# lvc-strobe-generator.net
KiCad netlist of a schematic drawn in EAGLE
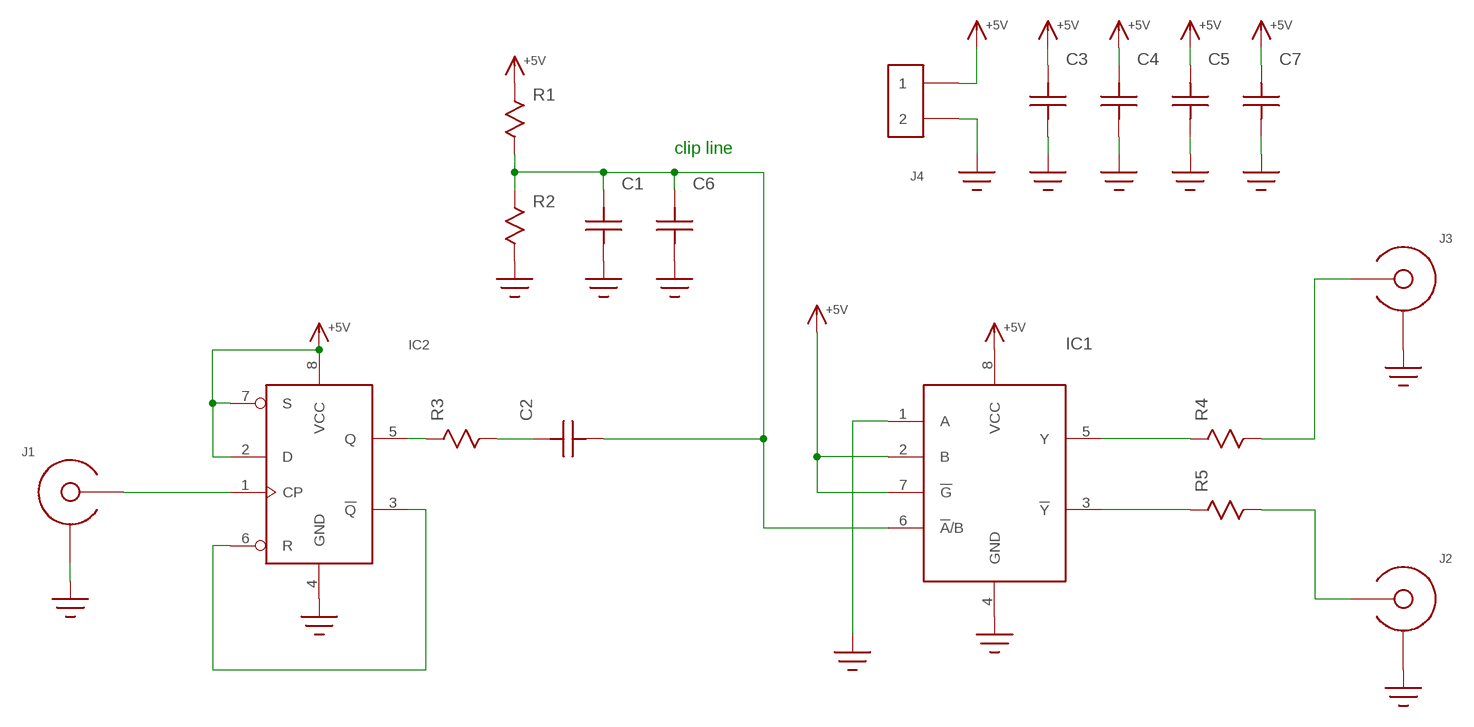
[diagram p0: schematic, sheet 1]

(export (version "E")
  (design (tool "Eeschema 10.0.6"))
  (components
    (comp (ref "C1") (value "C") (footprint "eagle-import:C0402") (libsource (lib "eagle-import") (part "C")))
    (comp (ref "C2") (value "C") (footprint "eagle-import:C0402") (libsource (lib "eagle-import") (part "C")))
    (comp (ref "C3")
      (value "C1206")
      (footprint "eagle-import:1206")
      (libsource (lib "eagle-import") (part "C1206"))
    )
    (comp (ref "C4")
      (value "C0603")
      (footprint "eagle-import:C0603")
      (libsource (lib "eagle-import") (part "C0603"))
    )
    (comp (ref "C5")
      (value "C0603")
      (footprint "eagle-import:C0603")
      (libsource (lib "eagle-import") (part "C0603"))
    )
    (comp (ref "C6") (value "C") (footprint "eagle-import:C0402") (libsource (lib "eagle-import") (part "C")))
    (comp (ref "C7")
      (value "C0603")
      (footprint "eagle-import:C0603")
      (libsource (lib "eagle-import") (part "C0603"))
    )
    (comp (ref "IC1")
      (value "74LVC2G157")
      (footprint "eagle-import:SSOP8")
      (libsource (lib "eagle-import") (part "74LVC2G157"))
    )
    (comp (ref "IC2")
      (value "74LVC2G74")
      (footprint "eagle-import:SSOP8")
      (libsource (lib "eagle-import") (part "74LVC2G74"))
    )
    (comp (ref "J1")
      (value "SMA-EDGE-LAUNCH4L-4020-TAPER-FIXED")
      (footprint "eagle-import:SMA_EDGE_LAUNCH_4L_4020_TAPER_FIXED")
      (libsource (lib "eagle-import") (part "SMA-EDGE-LAUNCH4L-4020-TAPER-FIXED"))
    )
    (comp (ref "J2")
      (value "SMA-EDGE-LAUNCH4L-4020-TAPER-FIXED")
      (footprint "eagle-import:SMA_EDGE_LAUNCH_4L_4020_TAPER_FIXED")
      (libsource (lib "eagle-import") (part "SMA-EDGE-LAUNCH4L-4020-TAPER-FIXED"))
    )
    (comp (ref "J3")
      (value "SMA-EDGE-LAUNCH4L-4020-TAPER-FIXED")
      (footprint "eagle-import:SMA_EDGE_LAUNCH_4L_4020_TAPER_FIXED")
      (libsource (lib "eagle-import") (part "SMA-EDGE-LAUNCH4L-4020-TAPER-FIXED"))
    )
    (comp (ref "J4")
      (value "HEADER_2PIN")
      (footprint "eagle-import:HEADER_2PIN")
      (libsource (lib "eagle-import") (part "HEADER_2PIN"))
    )
    (comp (ref "R1")
      (value "R0603")
      (footprint "eagle-import:R0603")
      (libsource (lib "eagle-import") (part "R0603"))
    )
    (comp (ref "R2")
      (value "R0603")
      (footprint "eagle-import:R0603")
      (libsource (lib "eagle-import") (part "R0603"))
    )
    (comp (ref "R3")
      (value "R0402")
      (footprint "eagle-import:0402")
      (libsource (lib "eagle-import") (part "R0402"))
    )
    (comp (ref "R4")
      (value "R0603")
      (footprint "eagle-import:R0603")
      (libsource (lib "eagle-import") (part "R0603"))
    )
    (comp (ref "R5")
      (value "R0603")
      (footprint "eagle-import:R0603")
      (libsource (lib "eagle-import") (part "R0603"))
    )
  )
  (nets
    (net (code "1") (name "+5V") (class "Default")
      (node (ref "C3") (pin "P$2") (pinfunction "P$2_P$2") (pintype "bidirectional"))
      (node (ref "C4") (pin "P$2") (pinfunction "P$2_P$2") (pintype "bidirectional"))
      (node (ref "C5") (pin "P$2") (pinfunction "P$2_P$2") (pintype "bidirectional"))
      (node (ref "C7") (pin "P$2") (pinfunction "P$2_P$2") (pintype "bidirectional"))
      (node (ref "IC1") (pin "2") (pinfunction "B_2") (pintype "bidirectional"))
      (node (ref "IC1") (pin "7") (pinfunction "~{G}_7") (pintype "bidirectional"))
      (node (ref "IC1") (pin "8") (pinfunction "VCC_8") (pintype "bidirectional"))
      (node (ref "IC2") (pin "2") (pinfunction "D_2") (pintype "bidirectional"))
      (node (ref "IC2") (pin "7") (pinfunction "S_7") (pintype "bidirectional"))
      (node (ref "IC2") (pin "8") (pinfunction "VCC_8") (pintype "bidirectional"))
      (node (ref "J4") (pin "1") (pinfunction "1_1") (pintype "bidirectional"))
      (node (ref "R1") (pin "P$1") (pinfunction "P$3_P$1") (pintype "bidirectional"))
    )
    (net (code "2") (name "GND") (class "Default")
      (node (ref "C1") (pin "1") (pinfunction "P$1_1") (pintype "bidirectional"))
      (node (ref "C3") (pin "P$1") (pinfunction "P$1_P$1") (pintype "bidirectional"))
      (node (ref "C4") (pin "P$1") (pinfunction "P$1_P$1") (pintype "bidirectional"))
      (node (ref "C5") (pin "P$1") (pinfunction "P$1_P$1") (pintype "bidirectional"))
      (node (ref "C6") (pin "1") (pinfunction "P$1_1") (pintype "bidirectional"))
      (node (ref "C7") (pin "P$1") (pinfunction "P$1_P$1") (pintype "bidirectional"))
      (node (ref "IC1") (pin "1") (pinfunction "A_1") (pintype "bidirectional"))
      (node (ref "IC1") (pin "4") (pinfunction "GND_4") (pintype "bidirectional"))
      (node (ref "IC2") (pin "4") (pinfunction "GND_4") (pintype "bidirectional"))
      (node (ref "J1") (pin "BOTTOM_GND") (pinfunction "SHIELD_BOTTOM_GND") (pintype "bidirectional"))
      (node (ref "J1") (pin "GND@1") (pinfunction "SHIELD_GND@1") (pintype "bidirectional"))
      (node (ref "J1") (pin "GND@14") (pinfunction "SHIELD_GND@14") (pintype "bidirectional"))
      (node (ref "J1") (pin "GND@15") (pinfunction "SHIELD_GND@15") (pintype "bidirectional"))
      (node (ref "J1") (pin "GND@16") (pinfunction "SHIELD_GND@16") (pintype "bidirectional"))
      (node (ref "J1") (pin "GND@17") (pinfunction "SHIELD_GND@17") (pintype "bidirectional"))
      (node (ref "J1") (pin "GND@2") (pinfunction "SHIELD_GND@2") (pintype "bidirectional"))
      (node (ref "J1") (pin "GND@3") (pinfunction "SHIELD_GND@3") (pintype "bidirectional"))
      (node (ref "J1") (pin "GND@4") (pinfunction "SHIELD_GND@4") (pintype "bidirectional"))
      (node (ref "J1") (pin "GND@5") (pinfunction "SHIELD_GND@5") (pintype "bidirectional"))
      (node (ref "J1") (pin "GND@6") (pinfunction "SHIELD_GND@6") (pintype "bidirectional"))
      (node (ref "J1") (pin "GND@7") (pinfunction "SHIELD_GND@7") (pintype "bidirectional"))
      (node (ref "J1") (pin "GND@8") (pinfunction "SHIELD_GND@8") (pintype "bidirectional"))
      (node (ref "J1") (pin "GND_PAD1") (pinfunction "SHIELD_GND_PAD1") (pintype "bidirectional"))
      (node (ref "J1") (pin "GND_PAD2") (pinfunction "SHIELD_GND_PAD2") (pintype "bidirectional"))
      (node (ref "J1") (pin "P$1") (pinfunction "SHIELD_P$1") (pintype "bidirectional"))
      (node (ref "J1") (pin "P$2") (pinfunction "SHIELD_P$2") (pintype "bidirectional"))
      (node (ref "J2") (pin "BOTTOM_GND") (pinfunction "SHIELD_BOTTOM_GND") (pintype "bidirectional"))
      (node (ref "J2") (pin "GND@1") (pinfunction "SHIELD_GND@1") (pintype "bidirectional"))
      (node (ref "J2") (pin "GND@14") (pinfunction "SHIELD_GND@14") (pintype "bidirectional"))
      (node (ref "J2") (pin "GND@15") (pinfunction "SHIELD_GND@15") (pintype "bidirectional"))
      (node (ref "J2") (pin "GND@16") (pinfunction "SHIELD_GND@16") (pintype "bidirectional"))
      (node (ref "J2") (pin "GND@17") (pinfunction "SHIELD_GND@17") (pintype "bidirectional"))
      (node (ref "J2") (pin "GND@2") (pinfunction "SHIELD_GND@2") (pintype "bidirectional"))
      (node (ref "J2") (pin "GND@3") (pinfunction "SHIELD_GND@3") (pintype "bidirectional"))
      (node (ref "J2") (pin "GND@4") (pinfunction "SHIELD_GND@4") (pintype "bidirectional"))
      (node (ref "J2") (pin "GND@5") (pinfunction "SHIELD_GND@5") (pintype "bidirectional"))
      (node (ref "J2") (pin "GND@6") (pinfunction "SHIELD_GND@6") (pintype "bidirectional"))
      (node (ref "J2") (pin "GND@7") (pinfunction "SHIELD_GND@7") (pintype "bidirectional"))
      (node (ref "J2") (pin "GND@8") (pinfunction "SHIELD_GND@8") (pintype "bidirectional"))
      (node (ref "J2") (pin "GND_PAD1") (pinfunction "SHIELD_GND_PAD1") (pintype "bidirectional"))
      (node (ref "J2") (pin "GND_PAD2") (pinfunction "SHIELD_GND_PAD2") (pintype "bidirectional"))
      (node (ref "J2") (pin "P$1") (pinfunction "SHIELD_P$1") (pintype "bidirectional"))
      (node (ref "J2") (pin "P$2") (pinfunction "SHIELD_P$2") (pintype "bidirectional"))
      (node (ref "J3") (pin "BOTTOM_GND") (pinfunction "SHIELD_BOTTOM_GND") (pintype "bidirectional"))
      (node (ref "J3") (pin "GND@1") (pinfunction "SHIELD_GND@1") (pintype "bidirectional"))
      (node (ref "J3") (pin "GND@14") (pinfunction "SHIELD_GND@14") (pintype "bidirectional"))
      (node (ref "J3") (pin "GND@15") (pinfunction "SHIELD_GND@15") (pintype "bidirectional"))
      (node (ref "J3") (pin "GND@16") (pinfunction "SHIELD_GND@16") (pintype "bidirectional"))
      (node (ref "J3") (pin "GND@17") (pinfunction "SHIELD_GND@17") (pintype "bidirectional"))
      (node (ref "J3") (pin "GND@2") (pinfunction "SHIELD_GND@2") (pintype "bidirectional"))
      (node (ref "J3") (pin "GND@3") (pinfunction "SHIELD_GND@3") (pintype "bidirectional"))
      (node (ref "J3") (pin "GND@4") (pinfunction "SHIELD_GND@4") (pintype "bidirectional"))
      (node (ref "J3") (pin "GND@5") (pinfunction "SHIELD_GND@5") (pintype "bidirectional"))
      (node (ref "J3") (pin "GND@6") (pinfunction "SHIELD_GND@6") (pintype "bidirectional"))
      (node (ref "J3") (pin "GND@7") (pinfunction "SHIELD_GND@7") (pintype "bidirectional"))
      (node (ref "J3") (pin "GND@8") (pinfunction "SHIELD_GND@8") (pintype "bidirectional"))
      (node (ref "J3") (pin "GND_PAD1") (pinfunction "SHIELD_GND_PAD1") (pintype "bidirectional"))
      (node (ref "J3") (pin "GND_PAD2") (pinfunction "SHIELD_GND_PAD2") (pintype "bidirectional"))
      (node (ref "J3") (pin "P$1") (pinfunction "SHIELD_P$1") (pintype "bidirectional"))
      (node (ref "J3") (pin "P$2") (pinfunction "SHIELD_P$2") (pintype "bidirectional"))
      (node (ref "J4") (pin "2") (pinfunction "2_2") (pintype "bidirectional"))
      (node (ref "R2") (pin "P$2") (pinfunction "P$4_P$2") (pintype "bidirectional"))
    )
    (net (code "3") (name "Net-(C1-P$2)") (class "Default")
      (node (ref "C1") (pin "2") (pinfunction "P$2_2") (pintype "bidirectional"))
      (node (ref "C2") (pin "1") (pinfunction "P$1_1") (pintype "bidirectional"))
      (node (ref "C6") (pin "2") (pinfunction "P$2_2") (pintype "bidirectional"))
      (node (ref "IC1") (pin "6") (pinfunction "~{A}/B_6") (pintype "bidirectional"))
      (node (ref "R1") (pin "P$2") (pinfunction "P$4_P$2") (pintype "bidirectional"))
      (node (ref "R2") (pin "P$1") (pinfunction "P$3_P$1") (pintype "bidirectional"))
    )
    (net (code "4") (name "Net-(C2-P$2)") (class "Default")
      (node (ref "C2") (pin "2") (pinfunction "P$2_2") (pintype "bidirectional"))
      (node (ref "R3") (pin "2") (pinfunction "P$4_2") (pintype "bidirectional"))
    )
    (net (code "5") (name "Net-(IC1-Y)") (class "Default")
      (node (ref "IC1") (pin "5") (pinfunction "Y_5") (pintype "bidirectional"))
      (node (ref "R4") (pin "P$1") (pinfunction "P$3_P$1") (pintype "bidirectional"))
    )
    (net (code "6") (name "Net-(IC1-~{Y})") (class "Default")
      (node (ref "IC1") (pin "3") (pinfunction "~{Y}_3") (pintype "bidirectional"))
      (node (ref "R5") (pin "P$1") (pinfunction "P$3_P$1") (pintype "bidirectional"))
    )
    (net (code "7") (name "Net-(IC2-CP)") (class "Default")
      (node (ref "IC2") (pin "1") (pinfunction "CP_1") (pintype "bidirectional"))
      (node (ref "J1") (pin "CENTER@1") (pinfunction "CENTER_CENTER@1") (pintype "bidirectional"))
      (node (ref "J1") (pin "P$3") (pinfunction "CENTER_P$3") (pintype "bidirectional"))
    )
    (net (code "8") (name "Net-(IC2-Q)") (class "Default")
      (node (ref "IC2") (pin "5") (pinfunction "Q_5") (pintype "bidirectional"))
      (node (ref "R3") (pin "1") (pinfunction "P$3_1") (pintype "bidirectional"))
    )
    (net (code "9") (name "Net-(IC2-R)") (class "Default")
      (node (ref "IC2") (pin "3") (pinfunction "~{Q}_3") (pintype "bidirectional"))
      (node (ref "IC2") (pin "6") (pinfunction "R_6") (pintype "bidirectional"))
    )
    (net (code "10") (name "Net-(R4-P$4)") (class "Default")
      (node (ref "J3") (pin "CENTER@1") (pinfunction "CENTER_CENTER@1") (pintype "bidirectional"))
      (node (ref "J3") (pin "P$3") (pinfunction "CENTER_P$3") (pintype "bidirectional"))
      (node (ref "R4") (pin "P$2") (pinfunction "P$4_P$2") (pintype "bidirectional"))
    )
    (net (code "11") (name "Net-(R5-P$4)") (class "Default")
      (node (ref "J2") (pin "CENTER@1") (pinfunction "CENTER_CENTER@1") (pintype "bidirectional"))
      (node (ref "J2") (pin "P$3") (pinfunction "CENTER_P$3") (pintype "bidirectional"))
      (node (ref "R5") (pin "P$2") (pinfunction "P$4_P$2") (pintype "bidirectional"))
    )
  )
)
